# ws2812-Breakout.net
KiCad netlist of a schematic drawn in EAGLE
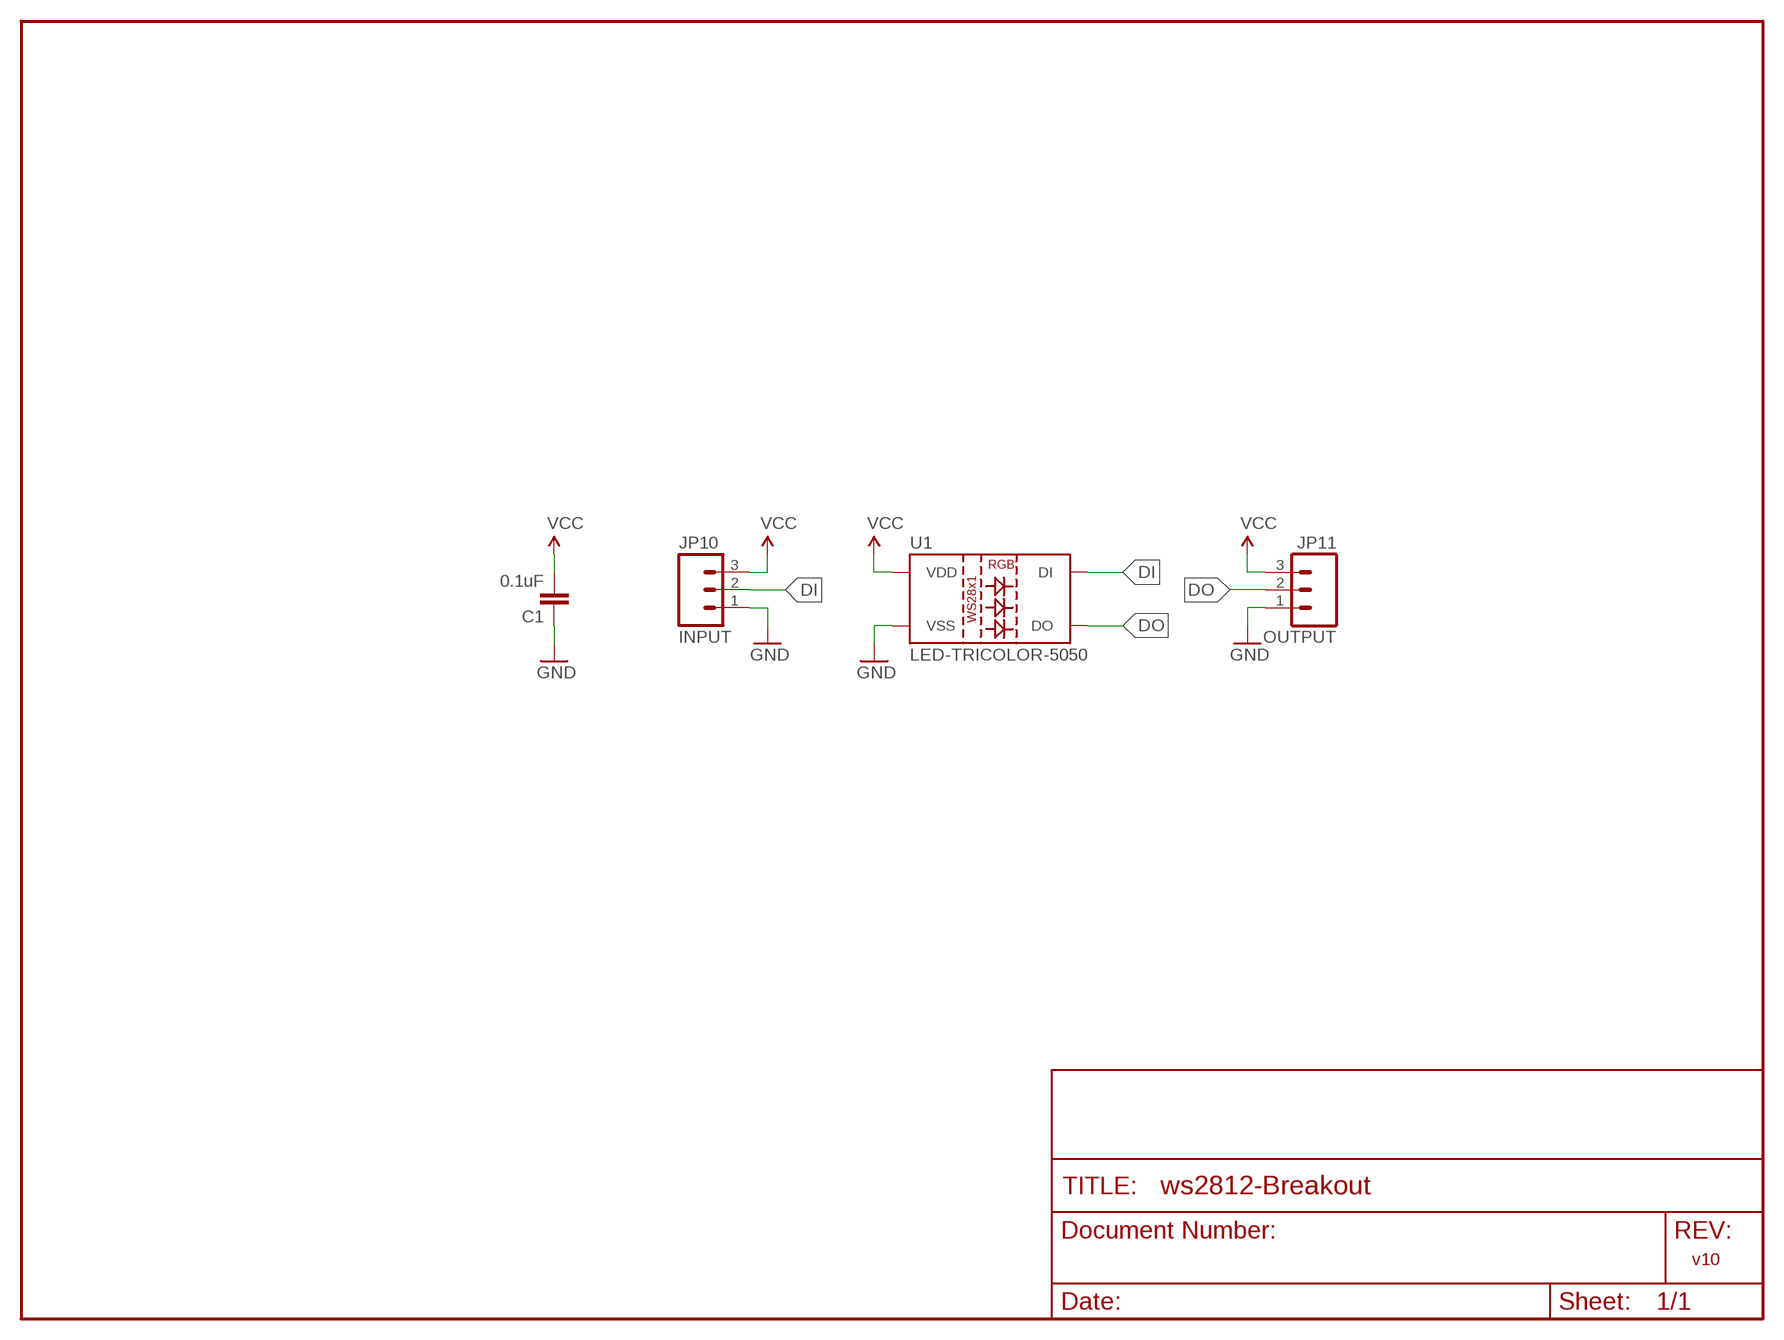
[diagram p0: schematic, sheet 1]

(export (version "E")
  (design (tool "Eeschema 10.0.6"))
  (components
    (comp (ref "C1")
      (value "0.1uF")
      (footprint "eagle-import:0603-CAP")
      (libsource (lib "eagle-import") (part "CAP0603-CAP"))
    )
    (comp (ref "JP10")
      (value "INPUT")
      (footprint "eagle-import:1X03")
      (libsource (lib "eagle-import") (part "M03PTH"))
    )
    (comp (ref "JP11")
      (value "OUTPUT")
      (footprint "eagle-import:1X03")
      (libsource (lib "eagle-import") (part "M03PTH"))
    )
    (comp (ref "U1")
      (value "LED-TRICOLOR-5050")
      (footprint "eagle-import:LED-TRICOLOR-5050-IC")
      (libsource (lib "eagle-import") (part "LED-TRICOLOR-5050-ICWS2811"))
    )
  )
  (nets
    (net (code "1") (name "DI") (class "Default")
      (node (ref "JP10") (pin "2") (pinfunction "2_2") (pintype "passive"))
      (node (ref "U1") (pin "2") (pinfunction "DI_2") (pintype "bidirectional"))
    )
    (net (code "2") (name "DO") (class "Default")
      (node (ref "JP11") (pin "2") (pinfunction "2_2") (pintype "passive"))
      (node (ref "U1") (pin "1") (pinfunction "DO_1") (pintype "bidirectional"))
    )
    (net (code "3") (name "GND") (class "Default")
      (node (ref "C1") (pin "1") (pinfunction "1_1") (pintype "passive"))
      (node (ref "JP10") (pin "1") (pinfunction "1_1") (pintype "passive"))
      (node (ref "JP11") (pin "1") (pinfunction "1_1") (pintype "passive"))
      (node (ref "U1") (pin "6") (pinfunction "VSS_6") (pintype "bidirectional"))
    )
    (net (code "4") (name "VCC") (class "Default")
      (node (ref "C1") (pin "2") (pinfunction "2_2") (pintype "passive"))
      (node (ref "JP10") (pin "3") (pinfunction "3_3") (pintype "passive"))
      (node (ref "JP11") (pin "3") (pinfunction "3_3") (pintype "passive"))
      (node (ref "U1") (pin "3") (pinfunction "VDD_3") (pintype "bidirectional"))
      (node (ref "U1") (pin "5") (pinfunction "VDD_5") (pintype "bidirectional"))
    )
  )
)
